# CDCEmu_Logic.net
KiCad netlist of a schematic drawn in EAGLE
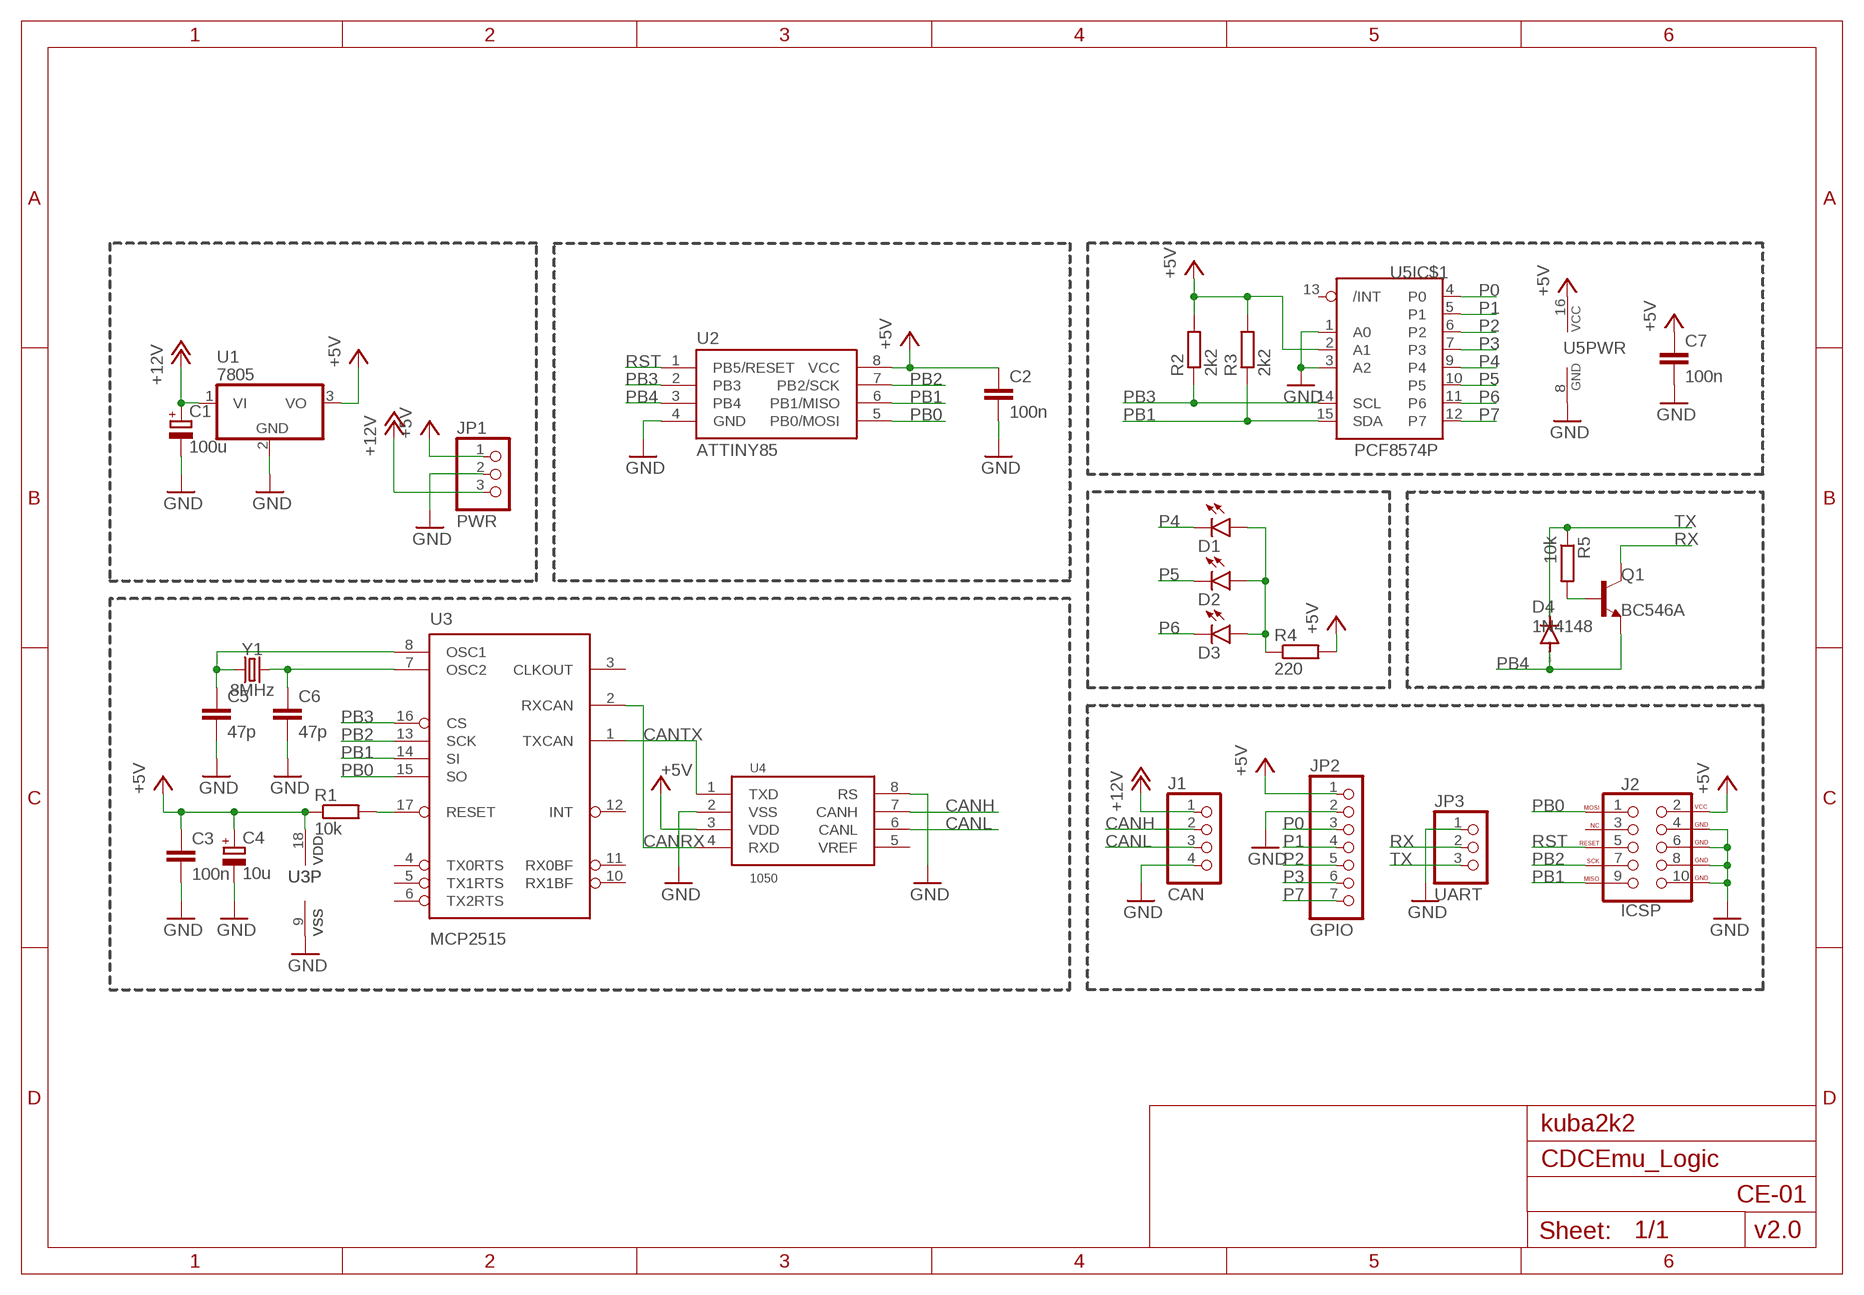
[diagram p0: schematic, sheet 1]

(export (version "E")
  (design (tool "Eeschema 10.0.6"))
  (components
    (comp (ref "C1")
      (value "100u")
      (footprint "eagle-import:E2,5-6")
      (libsource (lib "eagle-import") (part "CPOL-EUE2.5-6"))
    )
    (comp (ref "C2")
      (value "100n")
      (footprint "eagle-import:C050-024X044")
      (libsource (lib "eagle-import") (part "C-EU050-024X044"))
    )
    (comp (ref "C3")
      (value "100n")
      (footprint "eagle-import:C050-024X044")
      (libsource (lib "eagle-import") (part "C-EU050-024X044"))
    )
    (comp (ref "C4")
      (value "10u")
      (footprint "eagle-import:E1,8-4")
      (libsource (lib "eagle-import") (part "CPOL-EUE1.8-4"))
    )
    (comp (ref "C5")
      (value "47p")
      (footprint "eagle-import:C025-024X044")
      (libsource (lib "eagle-import") (part "C-EU025-024X044"))
    )
    (comp (ref "C6")
      (value "47p")
      (footprint "eagle-import:C025-024X044")
      (libsource (lib "eagle-import") (part "C-EU025-024X044"))
    )
    (comp (ref "C7")
      (value "100n")
      (footprint "eagle-import:C050-024X044")
      (libsource (lib "eagle-import") (part "C-EU050-024X044"))
    )
    (comp (ref "D1")
      (value "LED3MM")
      (footprint "eagle-import:LED3MM")
      (libsource (lib "eagle-import") (part "LED3MM"))
    )
    (comp (ref "D2")
      (value "LED3MM")
      (footprint "eagle-import:LED3MM")
      (libsource (lib "eagle-import") (part "LED3MM"))
    )
    (comp (ref "D3")
      (value "LED3MM")
      (footprint "eagle-import:LED3MM")
      (libsource (lib "eagle-import") (part "LED3MM"))
    )
    (comp (ref "D4")
      (value "1N4148")
      (footprint "eagle-import:DO35-7")
      (libsource (lib "eagle-import") (part "1N4148DO35-7"))
    )
    (comp (ref "J1")
      (value "CAN")
      (footprint "eagle-import:1X04")
      (libsource (lib "eagle-import") (part "PINHD-1X4"))
    )
    (comp (ref "J2")
      (value "ICSP")
      (footprint "eagle-import:2X5-SHROUDED_LOCK")
      (libsource (lib "eagle-import") (part "AVR_SPI_PROG_5X2LOCK"))
    )
    (comp (ref "JP1")
      (value "PWR")
      (footprint "eagle-import:1X03")
      (libsource (lib "eagle-import") (part "PINHD-1X3"))
    )
    (comp (ref "JP2")
      (value "GPIO")
      (footprint "eagle-import:1X07")
      (libsource (lib "eagle-import") (part "PINHD-1X7"))
    )
    (comp (ref "JP3")
      (value "UART")
      (footprint "eagle-import:1X03")
      (libsource (lib "eagle-import") (part "PINHD-1X3"))
    )
    (comp (ref "Q1")
      (value "BC546A")
      (footprint "eagle-import:TO92-EBC")
      (libsource (lib "eagle-import") (part "BC546A"))
    )
    (comp (ref "R1")
      (value "10k")
      (footprint "eagle-import:0204_5")
      (libsource (lib "eagle-import") (part "R-EU_0204/5"))
    )
    (comp (ref "R2")
      (value "2k2")
      (footprint "eagle-import:0204_7")
      (libsource (lib "eagle-import") (part "R-EU_0204/7"))
    )
    (comp (ref "R3")
      (value "2k2")
      (footprint "eagle-import:0204_7")
      (libsource (lib "eagle-import") (part "R-EU_0204/7"))
    )
    (comp (ref "R4")
      (value "220")
      (footprint "eagle-import:0204_7")
      (libsource (lib "eagle-import") (part "R-EU_0204/7"))
    )
    (comp (ref "R5")
      (value "10k")
      (footprint "eagle-import:0204_7")
      (libsource (lib "eagle-import") (part "R-EU_0204/7"))
    )
    (comp (ref "U1")
      (value "7805")
      (footprint "eagle-import:TO220V")
      (libsource (lib "eagle-import") (part "78TV05"))
    )
    (comp (ref "U2")
      (value "ATTINY85")
      (footprint "eagle-import:PDIP08_300MIL")
      (libsource (lib "eagle-import") (part "ATTINY85P-"))
    )
    (comp (ref "U3")
      (value "MCP2515")
      (footprint "eagle-import:SO18W")
      (libsource (lib "eagle-import") (part "MCP2515(MCP2510)SO"))
    )
    (comp (ref "U4")
      (value "1050")
      (footprint "eagle-import:SO08")
      (libsource (lib "eagle-import") (part "TJA1050"))
    )
    (comp (ref "U5")
      (value "PCF8574P")
      (footprint "eagle-import:DIL16")
      (libsource (lib "eagle-import") (part "PCF8574P"))
    )
    (comp (ref "Y1")
      (value "8MHz")
      (footprint "eagle-import:HC49U")
      (libsource (lib "eagle-import") (part "CRYSTALPTH-HC49UV"))
    )
  )
  (nets
    (net (code "1") (name "+5V") (class "Default")
      (node (ref "C2") (pin "1") (pinfunction "1_1") (pintype "passive"))
      (node (ref "C3") (pin "1") (pinfunction "1_1") (pintype "passive"))
      (node (ref "C4") (pin "+") (pinfunction "+_+") (pintype "passive"))
      (node (ref "C7") (pin "1") (pinfunction "1_1") (pintype "passive"))
      (node (ref "J2") (pin "2") (pinfunction "VCC_2") (pintype "power_in"))
      (node (ref "JP1") (pin "1") (pinfunction "1_1") (pintype "passive"))
      (node (ref "JP2") (pin "1") (pinfunction "1_1") (pintype "passive"))
      (node (ref "R1") (pin "1") (pinfunction "1_1") (pintype "passive"))
      (node (ref "R2") (pin "2") (pinfunction "2_2") (pintype "passive"))
      (node (ref "R3") (pin "2") (pinfunction "2_2") (pintype "passive"))
      (node (ref "R4") (pin "2") (pinfunction "2_2") (pintype "passive"))
      (node (ref "U1") (pin "3") (pinfunction "VO_3") (pintype "passive"))
      (node (ref "U2") (pin "8") (pinfunction "VCC_8") (pintype "power_in"))
      (node (ref "U3") (pin "18") (pinfunction "VDD_18") (pintype "power_in"))
      (node (ref "U4") (pin "3") (pinfunction "VDD_3") (pintype "power_in"))
      (node (ref "U5") (pin "16") (pinfunction "VCC_16") (pintype "power_in"))
      (node (ref "U5") (pin "2") (pinfunction "A1_2") (pintype "input"))
    )
    (net (code "2") (name "+12V") (class "Default")
      (node (ref "C1") (pin "+") (pinfunction "+_+") (pintype "passive"))
      (node (ref "J1") (pin "1") (pinfunction "1_1") (pintype "passive"))
      (node (ref "JP1") (pin "3") (pinfunction "3_3") (pintype "passive"))
      (node (ref "U1") (pin "1") (pinfunction "VI_1") (pintype "input"))
    )
    (net (code "3") (name "/CANH") (class "Default")
      (node (ref "J1") (pin "2") (pinfunction "2_2") (pintype "passive"))
      (node (ref "U4") (pin "7") (pinfunction "CANH_7") (pintype "bidirectional"))
    )
    (net (code "4") (name "/CANL") (class "Default")
      (node (ref "J1") (pin "3") (pinfunction "3_3") (pintype "passive"))
      (node (ref "U4") (pin "6") (pinfunction "CANL_6") (pintype "bidirectional"))
    )
    (net (code "5") (name "/CANRX") (class "Default")
      (node (ref "U3") (pin "2") (pinfunction "RXCAN_2") (pintype "input"))
      (node (ref "U4") (pin "4") (pinfunction "RXD_4") (pintype "output"))
    )
    (net (code "6") (name "/CANTX") (class "Default")
      (node (ref "U3") (pin "1") (pinfunction "TXCAN_1") (pintype "output"))
      (node (ref "U4") (pin "1") (pinfunction "TXD_1") (pintype "input"))
    )
    (net (code "7") (name "/P0") (class "Default")
      (node (ref "JP2") (pin "3") (pinfunction "3_3") (pintype "passive"))
      (node (ref "U5") (pin "4") (pinfunction "P0_4") (pintype "bidirectional"))
    )
    (net (code "8") (name "/P1") (class "Default")
      (node (ref "JP2") (pin "4") (pinfunction "4_4") (pintype "passive"))
      (node (ref "U5") (pin "5") (pinfunction "P1_5") (pintype "bidirectional"))
    )
    (net (code "9") (name "/P2") (class "Default")
      (node (ref "JP2") (pin "5") (pinfunction "5_5") (pintype "passive"))
      (node (ref "U5") (pin "6") (pinfunction "P2_6") (pintype "bidirectional"))
    )
    (net (code "10") (name "/P3") (class "Default")
      (node (ref "JP2") (pin "6") (pinfunction "6_6") (pintype "passive"))
      (node (ref "U5") (pin "7") (pinfunction "P3_7") (pintype "bidirectional"))
    )
    (net (code "11") (name "/P4") (class "Default")
      (node (ref "D1") (pin "K") (pinfunction "C_K") (pintype "passive"))
      (node (ref "U5") (pin "9") (pinfunction "P4_9") (pintype "bidirectional"))
    )
    (net (code "12") (name "/P5") (class "Default")
      (node (ref "D2") (pin "K") (pinfunction "C_K") (pintype "passive"))
      (node (ref "U5") (pin "10") (pinfunction "P5_10") (pintype "bidirectional"))
    )
    (net (code "13") (name "/P6") (class "Default")
      (node (ref "D3") (pin "K") (pinfunction "C_K") (pintype "passive"))
      (node (ref "U5") (pin "11") (pinfunction "P6_11") (pintype "bidirectional"))
    )
    (net (code "14") (name "/P7") (class "Default")
      (node (ref "JP2") (pin "7") (pinfunction "7_7") (pintype "passive"))
      (node (ref "U5") (pin "12") (pinfunction "P7_12") (pintype "bidirectional"))
    )
    (net (code "15") (name "/PB0") (class "Default")
      (node (ref "J2") (pin "1") (pinfunction "MOSI_1") (pintype "passive"))
      (node (ref "U2") (pin "5") (pinfunction "PB0/MOSI_5") (pintype "bidirectional"))
      (node (ref "U3") (pin "15") (pinfunction "SO_15") (pintype "output"))
    )
    (net (code "16") (name "/PB1") (class "Default")
      (node (ref "J2") (pin "9") (pinfunction "MISO_9") (pintype "passive"))
      (node (ref "R3") (pin "1") (pinfunction "1_1") (pintype "passive"))
      (node (ref "U2") (pin "6") (pinfunction "PB1/MISO_6") (pintype "bidirectional"))
      (node (ref "U3") (pin "14") (pinfunction "SI_14") (pintype "input"))
      (node (ref "U5") (pin "15") (pinfunction "SDA_15") (pintype "bidirectional"))
    )
    (net (code "17") (name "/PB2") (class "Default")
      (node (ref "J2") (pin "7") (pinfunction "SCK_7") (pintype "passive"))
      (node (ref "U2") (pin "7") (pinfunction "PB2/SCK_7") (pintype "bidirectional"))
      (node (ref "U3") (pin "13") (pinfunction "SCK_13") (pintype "input"))
    )
    (net (code "18") (name "/PB3") (class "Default")
      (node (ref "R2") (pin "1") (pinfunction "1_1") (pintype "passive"))
      (node (ref "U2") (pin "2") (pinfunction "PB3_2") (pintype "bidirectional"))
      (node (ref "U3") (pin "16") (pinfunction "CS_16") (pintype "input"))
      (node (ref "U5") (pin "14") (pinfunction "SCL_14") (pintype "input"))
    )
    (net (code "19") (name "/PB4") (class "Default")
      (node (ref "D4") (pin "A") (pinfunction "A_A") (pintype "passive"))
      (node (ref "Q1") (pin "E") (pinfunction "E_E") (pintype "passive"))
      (node (ref "U2") (pin "3") (pinfunction "PB4_3") (pintype "bidirectional"))
    )
    (net (code "20") (name "/RST") (class "Default")
      (node (ref "J2") (pin "5") (pinfunction "RESET_5") (pintype "passive"))
      (node (ref "U2") (pin "1") (pinfunction "PB5/RESET_1") (pintype "bidirectional"))
    )
    (net (code "21") (name "/RX") (class "Default")
      (node (ref "JP3") (pin "2") (pinfunction "2_2") (pintype "passive"))
      (node (ref "Q1") (pin "C") (pinfunction "C_C") (pintype "passive"))
    )
    (net (code "22") (name "/TX") (class "Default")
      (node (ref "D4") (pin "C") (pinfunction "C_C") (pintype "passive"))
      (node (ref "JP3") (pin "3") (pinfunction "3_3") (pintype "passive"))
      (node (ref "R5") (pin "1") (pinfunction "1_1") (pintype "passive"))
    )
    (net (code "23") (name "GND") (class "Default")
      (node (ref "C1") (pin "-") (pinfunction "-_-") (pintype "passive"))
      (node (ref "C2") (pin "2") (pinfunction "2_2") (pintype "passive"))
      (node (ref "C3") (pin "2") (pinfunction "2_2") (pintype "passive"))
      (node (ref "C4") (pin "-") (pinfunction "-_-") (pintype "passive"))
      (node (ref "C5") (pin "2") (pinfunction "2_2") (pintype "passive"))
      (node (ref "C6") (pin "2") (pinfunction "2_2") (pintype "passive"))
      (node (ref "C7") (pin "2") (pinfunction "2_2") (pintype "passive"))
      (node (ref "J1") (pin "4") (pinfunction "4_4") (pintype "passive"))
      (node (ref "J2") (pin "10") (pinfunction "GND_10") (pintype "power_in"))
      (node (ref "J2") (pin "4") (pinfunction "GND_4") (pintype "power_in"))
      (node (ref "J2") (pin "6") (pinfunction "GND_6") (pintype "power_in"))
      (node (ref "J2") (pin "8") (pinfunction "GND_8") (pintype "power_in"))
      (node (ref "JP1") (pin "2") (pinfunction "2_2") (pintype "passive"))
      (node (ref "JP2") (pin "2") (pinfunction "2_2") (pintype "passive"))
      (node (ref "JP3") (pin "1") (pinfunction "1_1") (pintype "passive"))
      (node (ref "U1") (pin "2") (pinfunction "GND_2") (pintype "passive"))
      (node (ref "U2") (pin "4") (pinfunction "GND_4") (pintype "power_in"))
      (node (ref "U3") (pin "9") (pinfunction "VSS_9") (pintype "power_in"))
      (node (ref "U4") (pin "2") (pinfunction "VSS_2") (pintype "power_in"))
      (node (ref "U4") (pin "8") (pinfunction "RS_8") (pintype "input"))
      (node (ref "U5") (pin "1") (pinfunction "A0_1") (pintype "input"))
      (node (ref "U5") (pin "3") (pinfunction "A2_3") (pintype "input"))
      (node (ref "U5") (pin "8") (pinfunction "GND_8") (pintype "power_in"))
    )
    (net (code "24") (name "Net-(D1-PadA)") (class "Default")
      (node (ref "D1") (pin "A") (pinfunction "A_A") (pintype "passive"))
      (node (ref "D2") (pin "A") (pinfunction "A_A") (pintype "passive"))
      (node (ref "D3") (pin "A") (pinfunction "A_A") (pintype "passive"))
      (node (ref "R4") (pin "1") (pinfunction "1_1") (pintype "passive"))
    )
    (net (code "25") (name "Net-(Q1-PadB)") (class "Default")
      (node (ref "Q1") (pin "B") (pinfunction "B_B") (pintype "passive"))
      (node (ref "R5") (pin "2") (pinfunction "2_2") (pintype "passive"))
    )
    (net (code "26") (name "Net-(U3A-OSC1)") (class "Default")
      (node (ref "C5") (pin "1") (pinfunction "1_1") (pintype "passive"))
      (node (ref "U3") (pin "8") (pinfunction "OSC1_8") (pintype "input"))
      (node (ref "Y1") (pin "1") (pinfunction "1_1") (pintype "passive"))
    )
    (net (code "27") (name "Net-(U3A-OSC2)") (class "Default")
      (node (ref "C6") (pin "1") (pinfunction "1_1") (pintype "passive"))
      (node (ref "U3") (pin "7") (pinfunction "OSC2_7") (pintype "output"))
      (node (ref "Y1") (pin "2") (pinfunction "2_2") (pintype "passive"))
    )
    (net (code "28") (name "Net-(U3A-RESET)") (class "Default")
      (node (ref "R1") (pin "2") (pinfunction "2_2") (pintype "passive"))
      (node (ref "U3") (pin "17") (pinfunction "RESET_17") (pintype "input"))
    )
    (net (code "29") (name "unconnected-(J2-NC-Pad3)") (class "Default")
      (node (ref "J2") (pin "3") (pinfunction "NC_3") (pintype "no_connect"))
    )
    (net (code "30") (name "unconnected-(U3A-CLKOUT-Pad3)") (class "Default")
      (node (ref "U3") (pin "3") (pinfunction "CLKOUT_3") (pintype "output"))
    )
    (net (code "31") (name "unconnected-(U3A-INT-Pad12)") (class "Default")
      (node (ref "U3") (pin "12") (pinfunction "INT_12") (pintype "output"))
    )
    (net (code "32") (name "unconnected-(U3A-RX0BF-Pad11)") (class "Default")
      (node (ref "U3") (pin "11") (pinfunction "RX0BF_11") (pintype "output"))
    )
    (net (code "33") (name "unconnected-(U3A-RX1BF-Pad10)") (class "Default")
      (node (ref "U3") (pin "10") (pinfunction "RX1BF_10") (pintype "output"))
    )
    (net (code "34") (name "unconnected-(U3A-TX0RTS-Pad4)") (class "Default")
      (node (ref "U3") (pin "4") (pinfunction "TX0RTS_4") (pintype "input"))
    )
    (net (code "35") (name "unconnected-(U3A-TX1RTS-Pad5)") (class "Default")
      (node (ref "U3") (pin "5") (pinfunction "TX1RTS_5") (pintype "input"))
    )
    (net (code "36") (name "unconnected-(U3A-TX2RTS-Pad6)") (class "Default")
      (node (ref "U3") (pin "6") (pinfunction "TX2RTS_6") (pintype "input"))
    )
    (net (code "37") (name "unconnected-(U4-VREF-Pad5)") (class "Default")
      (node (ref "U4") (pin "5") (pinfunction "VREF_5") (pintype "passive"))
    )
    (net (code "38") (name "unconnected-(U5A-{slash}INT-Pad13)") (class "Default")
      (node (ref "U5") (pin "13") (pinfunction "/INT_13") (pintype "output"))
    )
  )
)
